# RPi_breakout.net
KiCad netlist of a schematic drawn in EAGLE
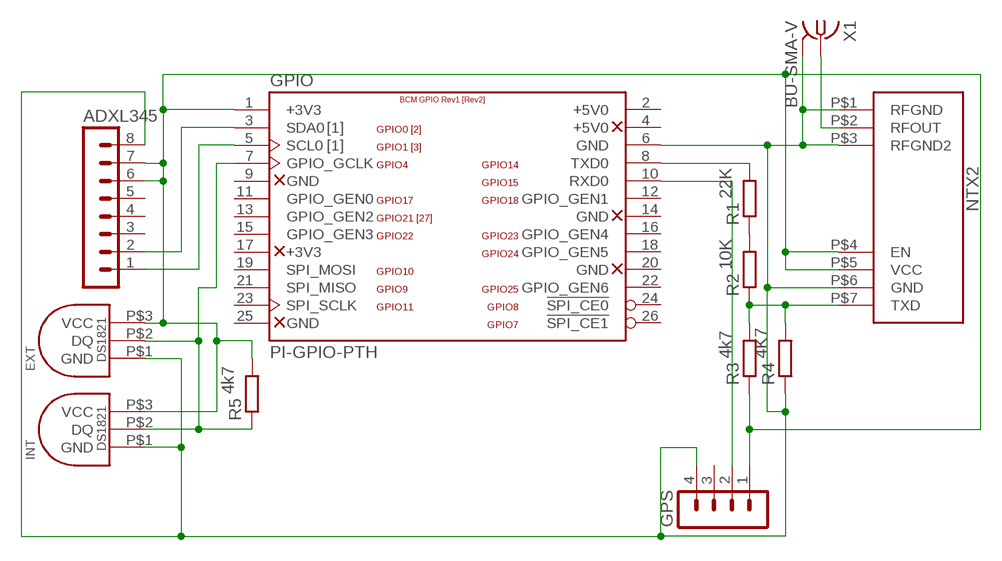
[diagram p0: schematic, sheet 1]

(export (version "E")
  (design (tool "Eeschema 10.0.6"))
  (components
    (comp (ref "ADXL345")
      (value "MA08-1")
      (footprint "eagle-import:MA08-1")
      (libsource (lib "eagle-import") (part "MA08-1"))
    )
    (comp (ref "EXT")
      (value "DS1821")
      (footprint "eagle-import:DS1821")
      (libsource (lib "eagle-import") (part "DS1821"))
    )
    (comp (ref "GPIO")
      (value "PI-GPIO-PTH")
      (footprint "eagle-import:GPIO-CONNECTOR")
      (libsource (lib "eagle-import") (part "PI-GPIO-PTH"))
    )
    (comp (ref "GPS")
      (value "MA04-1")
      (footprint "eagle-import:MA04-1")
      (libsource (lib "eagle-import") (part "MA04-1"))
    )
    (comp (ref "INT")
      (value "DS1821")
      (footprint "eagle-import:DS1821")
      (libsource (lib "eagle-import") (part "DS1821"))
    )
    (comp (ref "NTX2")
      (value "NTX2")
      (footprint "eagle-import:NTX2")
      (libsource (lib "eagle-import") (part "NTX2"))
    )
    (comp (ref "R1")
      (value "R-EU_0207/10")
      (footprint "eagle-import:0207_10")
      (fields (field (name "R1") "22K"))
      (libsource (lib "eagle-import") (part "R-EU_0207/10"))
    )
    (comp (ref "R2")
      (value "R-EU_0207/10")
      (footprint "eagle-import:0207_10")
      (fields (field (name "R1") "10K"))
      (libsource (lib "eagle-import") (part "R-EU_0207/10"))
    )
    (comp (ref "R3")
      (value "R-EU_0207/10")
      (footprint "eagle-import:0207_10")
      (fields (field (name "R3") "4k7"))
      (libsource (lib "eagle-import") (part "R-EU_0207/10"))
    )
    (comp (ref "R4")
      (value "R-EU_0207/10")
      (footprint "eagle-import:0207_10")
      (fields (field (name "R2") "4K7"))
      (libsource (lib "eagle-import") (part "R-EU_0207/10"))
    )
    (comp (ref "R5")
      (value "R-EU_0207/10")
      (footprint "eagle-import:0207_10")
      (fields (field (name "R3") "4k7"))
      (libsource (lib "eagle-import") (part "R-EU_0207/10"))
    )
    (comp (ref "X1")
      (value "BU-SMA-V")
      (footprint "eagle-import:BU-SMA-V")
      (libsource (lib "eagle-import") (part "BU-SMA-V"))
    )
  )
  (nets
    (net (code "1") (name "/+5V0") (class "Default")
      (node (ref "GPIO") (pin "2") (pinfunction "+5V0_2") (pintype "power_in"))
    )
    (net (code "2") (name "Net-(EXT-DQ)") (class "Default")
      (node (ref "EXT") (pin "P$2") (pinfunction "DQ_P$2") (pintype "bidirectional"))
      (node (ref "GPIO") (pin "7") (pinfunction "GPIO_GCLK_7") (pintype "bidirectional"))
      (node (ref "INT") (pin "P$2") (pinfunction "DQ_P$2") (pintype "bidirectional"))
      (node (ref "R5") (pin "1") (pinfunction "1_1") (pintype "passive"))
    )
    (net (code "3") (name "Net-(EXT-GND)") (class "Default")
      (node (ref "ADXL345") (pin "8") (pinfunction "8_8") (pintype "passive"))
      (node (ref "EXT") (pin "P$1") (pinfunction "GND_P$1") (pintype "power_in"))
      (node (ref "GPIO") (pin "6") (pinfunction "GND_6") (pintype "power_in"))
      (node (ref "GPS") (pin "4") (pinfunction "4_4") (pintype "passive"))
      (node (ref "INT") (pin "P$1") (pinfunction "GND_P$1") (pintype "power_in"))
      (node (ref "NTX2") (pin "P$1") (pinfunction "RFGND_P$1") (pintype "passive"))
      (node (ref "NTX2") (pin "P$3") (pinfunction "RFGND2_P$3") (pintype "passive"))
      (node (ref "NTX2") (pin "P$6") (pinfunction "GND_P$6") (pintype "power_in"))
      (node (ref "R4") (pin "1") (pinfunction "1_1") (pintype "passive"))
      (node (ref "X1") (pin "2") (pinfunction "2_2") (pintype "passive"))
      (node (ref "X1") (pin "3") (pinfunction "2_3") (pintype "passive"))
      (node (ref "X1") (pin "4") (pinfunction "2_4") (pintype "passive"))
      (node (ref "X1") (pin "5") (pinfunction "2_5") (pintype "passive"))
    )
    (net (code "4") (name "Net-(EXT-VCC)") (class "Default")
      (node (ref "ADXL345") (pin "6") (pinfunction "6_6") (pintype "passive"))
      (node (ref "ADXL345") (pin "7") (pinfunction "7_7") (pintype "passive"))
      (node (ref "EXT") (pin "P$3") (pinfunction "VCC_P$3") (pintype "power_in"))
      (node (ref "GPIO") (pin "1") (pinfunction "+3V3_1") (pintype "power_in"))
      (node (ref "GPS") (pin "1") (pinfunction "1_1") (pintype "passive"))
      (node (ref "INT") (pin "P$3") (pinfunction "VCC_P$3") (pintype "power_in"))
      (node (ref "NTX2") (pin "P$4") (pinfunction "EN_P$4") (pintype "bidirectional"))
      (node (ref "NTX2") (pin "P$5") (pinfunction "VCC_P$5") (pintype "power_in"))
      (node (ref "R3") (pin "1") (pinfunction "1_1") (pintype "passive"))
      (node (ref "R5") (pin "2") (pinfunction "2_2") (pintype "passive"))
    )
    (net (code "5") (name "Net-(GPIO-RXD0)") (class "Default")
      (node (ref "GPIO") (pin "10") (pinfunction "RXD0_10") (pintype "bidirectional"))
      (node (ref "GPS") (pin "2") (pinfunction "2_2") (pintype "passive"))
    )
    (net (code "6") (name "Net-(GPIO-SCL0)") (class "Default")
      (node (ref "ADXL345") (pin "1") (pinfunction "1_1") (pintype "passive"))
      (node (ref "GPIO") (pin "5") (pinfunction "SCL0_5") (pintype "bidirectional"))
    )
    (net (code "7") (name "Net-(GPIO-SDA0)") (class "Default")
      (node (ref "ADXL345") (pin "2") (pinfunction "2_2") (pintype "passive"))
      (node (ref "GPIO") (pin "3") (pinfunction "SDA0_3") (pintype "bidirectional"))
    )
    (net (code "8") (name "Net-(GPIO-TXD0)") (class "Default")
      (node (ref "GPIO") (pin "8") (pinfunction "TXD0_8") (pintype "bidirectional"))
      (node (ref "R1") (pin "2") (pinfunction "2_2") (pintype "passive"))
    )
    (net (code "9") (name "Net-(NTX2-RFOUT)") (class "Default")
      (node (ref "NTX2") (pin "P$2") (pinfunction "RFOUT_P$2") (pintype "passive"))
      (node (ref "X1") (pin "1") (pinfunction "1_1") (pintype "passive"))
    )
    (net (code "10") (name "Net-(NTX2-TXD)") (class "Default")
      (node (ref "NTX2") (pin "P$7") (pinfunction "TXD_P$7") (pintype "input"))
      (node (ref "R2") (pin "1") (pinfunction "1_1") (pintype "passive"))
      (node (ref "R3") (pin "2") (pinfunction "2_2") (pintype "passive"))
      (node (ref "R4") (pin "2") (pinfunction "2_2") (pintype "passive"))
    )
    (net (code "11") (name "Net-(R1-Pad1)") (class "Default")
      (node (ref "R1") (pin "1") (pinfunction "1_1") (pintype "passive"))
      (node (ref "R2") (pin "2") (pinfunction "2_2") (pintype "passive"))
    )
    (net (code "12") (name "unconnected-(ADXL345-Pad3)") (class "Default")
      (node (ref "ADXL345") (pin "3") (pinfunction "3_3") (pintype "passive"))
    )
    (net (code "13") (name "unconnected-(ADXL345-Pad4)") (class "Default")
      (node (ref "ADXL345") (pin "4") (pinfunction "4_4") (pintype "passive"))
    )
    (net (code "14") (name "unconnected-(ADXL345-Pad5)") (class "Default")
      (node (ref "ADXL345") (pin "5") (pinfunction "5_5") (pintype "passive"))
    )
    (net (code "15") (name "unconnected-(GPIO-+3V3-Pad17)") (class "Default")
      (node (ref "GPIO") (pin "17") (pinfunction "+3V3_17") (pintype "no_connect"))
    )
    (net (code "16") (name "unconnected-(GPIO-+5V0-Pad4)") (class "Default")
      (node (ref "GPIO") (pin "4") (pinfunction "+5V0_4") (pintype "no_connect"))
    )
    (net (code "17") (name "unconnected-(GPIO-GND-Pad9)") (class "Default")
      (node (ref "GPIO") (pin "9") (pinfunction "GND_9") (pintype "no_connect"))
    )
    (net (code "18") (name "unconnected-(GPIO-GND-Pad14)") (class "Default")
      (node (ref "GPIO") (pin "14") (pinfunction "GND_14") (pintype "no_connect"))
    )
    (net (code "19") (name "unconnected-(GPIO-GND-Pad20)") (class "Default")
      (node (ref "GPIO") (pin "20") (pinfunction "GND_20") (pintype "no_connect"))
    )
    (net (code "20") (name "unconnected-(GPIO-GND-Pad25)") (class "Default")
      (node (ref "GPIO") (pin "25") (pinfunction "GND_25") (pintype "no_connect"))
    )
    (net (code "21") (name "unconnected-(GPIO-GPIO_GEN0-Pad11)") (class "Default")
      (node (ref "GPIO") (pin "11") (pinfunction "GPIO_GEN0_11") (pintype "bidirectional"))
    )
    (net (code "22") (name "unconnected-(GPIO-GPIO_GEN1-Pad12)") (class "Default")
      (node (ref "GPIO") (pin "12") (pinfunction "GPIO_GEN1_12") (pintype "bidirectional"))
    )
    (net (code "23") (name "unconnected-(GPIO-GPIO_GEN2-Pad13)") (class "Default")
      (node (ref "GPIO") (pin "13") (pinfunction "GPIO_GEN2_13") (pintype "bidirectional"))
    )
    (net (code "24") (name "unconnected-(GPIO-GPIO_GEN3-Pad15)") (class "Default")
      (node (ref "GPIO") (pin "15") (pinfunction "GPIO_GEN3_15") (pintype "bidirectional"))
    )
    (net (code "25") (name "unconnected-(GPIO-GPIO_GEN4-Pad16)") (class "Default")
      (node (ref "GPIO") (pin "16") (pinfunction "GPIO_GEN4_16") (pintype "bidirectional"))
    )
    (net (code "26") (name "unconnected-(GPIO-GPIO_GEN5-Pad18)") (class "Default")
      (node (ref "GPIO") (pin "18") (pinfunction "GPIO_GEN5_18") (pintype "bidirectional"))
    )
    (net (code "27") (name "unconnected-(GPIO-GPIO_GEN6-Pad22)") (class "Default")
      (node (ref "GPIO") (pin "22") (pinfunction "GPIO_GEN6_22") (pintype "bidirectional"))
    )
    (net (code "28") (name "unconnected-(GPIO-SPI_MISO-Pad21)") (class "Default")
      (node (ref "GPIO") (pin "21") (pinfunction "SPI_MISO_21") (pintype "bidirectional"))
    )
    (net (code "29") (name "unconnected-(GPIO-SPI_MOSI-Pad19)") (class "Default")
      (node (ref "GPIO") (pin "19") (pinfunction "SPI_MOSI_19") (pintype "bidirectional"))
    )
    (net (code "30") (name "unconnected-(GPIO-SPI_SCLK-Pad23)") (class "Default")
      (node (ref "GPIO") (pin "23") (pinfunction "SPI_SCLK_23") (pintype "bidirectional"))
    )
    (net (code "31") (name "unconnected-(GPIO-~{SPI_CE0}-Pad24)") (class "Default")
      (node (ref "GPIO") (pin "24") (pinfunction "~{SPI_CE0}_24") (pintype "bidirectional"))
    )
    (net (code "32") (name "unconnected-(GPIO-~{SPI_CE1}-Pad26)") (class "Default")
      (node (ref "GPIO") (pin "26") (pinfunction "~{SPI_CE1}_26") (pintype "bidirectional"))
    )
    (net (code "33") (name "unconnected-(GPS-Pad3)") (class "Default")
      (node (ref "GPS") (pin "3") (pinfunction "3_3") (pintype "passive"))
    )
  )
)
